# Micro-Controller_Unit.net
KiCad netlist of a schematic drawn in Altium Designer
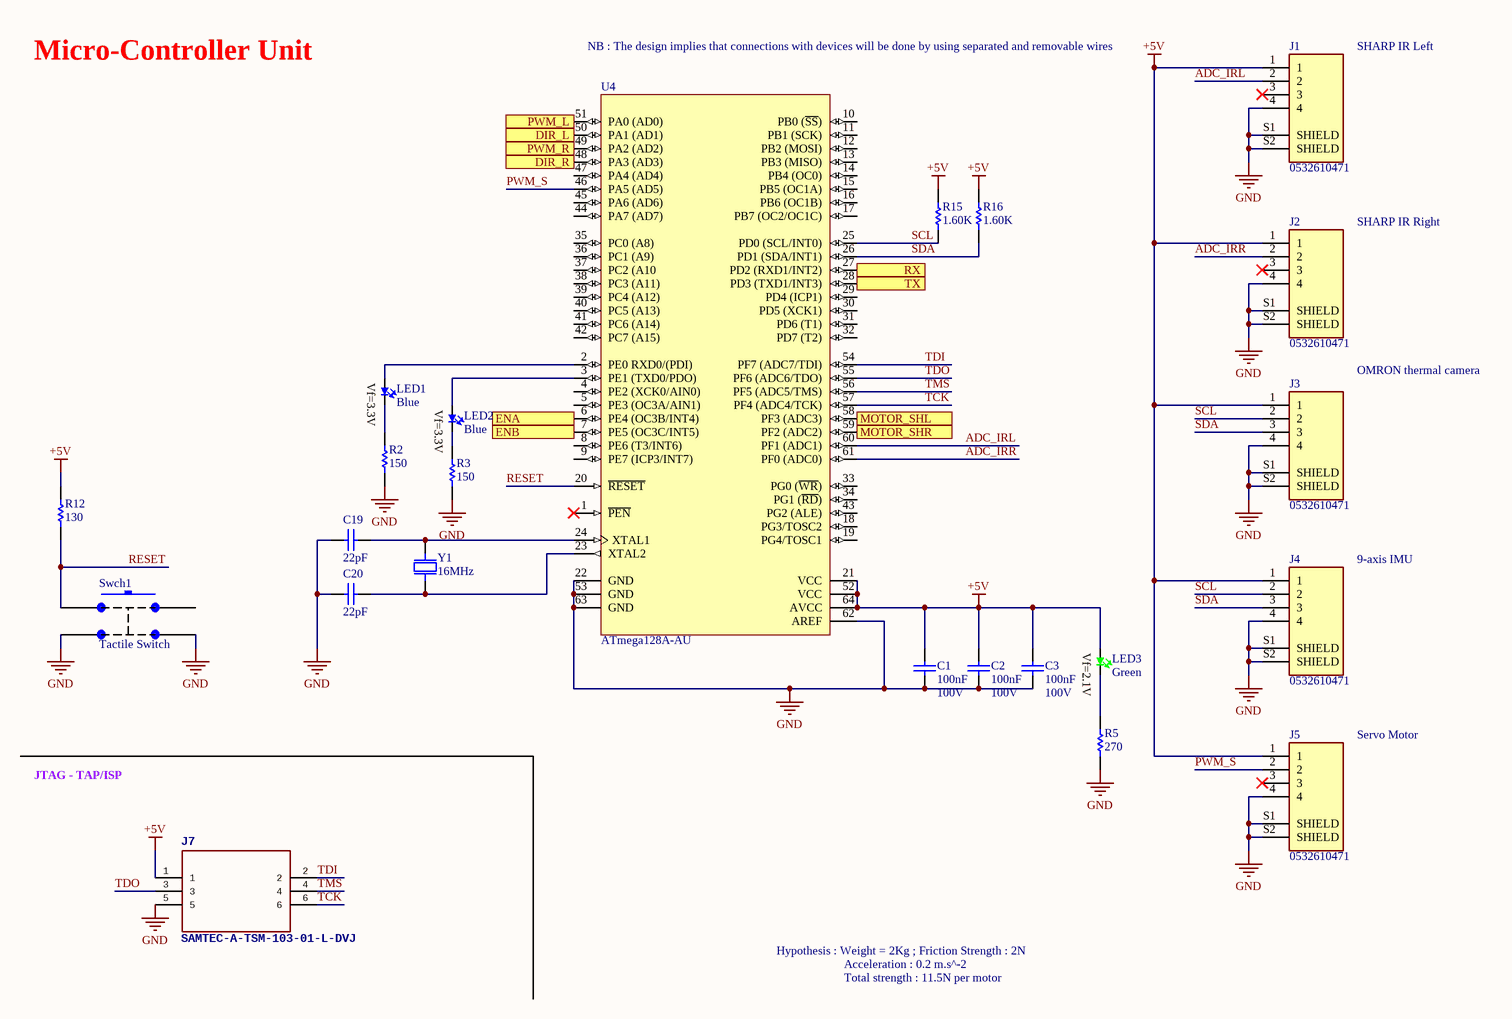
[diagram p0: Micro-Controller Unit.SchDoc]

(export (version "E")
  (design (tool "Eeschema 10.0.6"))
  (components
    (comp (ref "C1")
      (value "100nF")
      (footprint "CC0603 x 0.95mm")
      (description "0.1µF ±10% 100V Ceramic Capacitor X7R 0603 (1608 Metric)")
      (fields
        (field (name "MANUFACTURER") "Yageo")
        (field (name "PART NUMBER") "CS0603KRX7R0BB104")
        (field (name "VOLTAGE - RATED") "100V")
      )
      (libsource (lib "MLCC") (part "CAP"))
    )
    (comp (ref "C2")
      (value "100nF")
      (footprint "CAP-SMT:CC0603 x 0.95mm")
      (description "0.1µF ±10% 100V Ceramic Capacitor X7R 0603 (1608 Metric)")
      (fields
        (field (name "MANUFACTURER") "Yageo")
        (field (name "PART NUMBER") "CS0603KRX7R0BB104")
        (field (name "VOLTAGE - RATED") "100V")
      )
      (libsource (lib "MLCC") (part "CAP"))
    )
    (comp (ref "C3")
      (value "100nF")
      (footprint "CAP-SMT:CC0603 x 0.95mm")
      (description "0.1µF ±10% 100V Ceramic Capacitor X7R 0603 (1608 Metric)")
      (fields
        (field (name "MANUFACTURER") "Yageo")
        (field (name "PART NUMBER") "CS0603KRX7R0BB104")
        (field (name "VOLTAGE - RATED") "100V")
      )
      (libsource (lib "MLCC") (part "CAP"))
    )
    (comp (ref "C19")
      (value "22pF")
      (footprint "CC0201 x 0.33mm")
      (description "22pF ±2% 50V Ceramic Capacitor C0G, NP0 0201 (0603 Metric)")
      (fields (field (name "MANUFACTURER") "Yageo") (field (name "PART NUMBER") "CC0201GRNPO9BN220"))
      (libsource (lib "MLCC") (part "CAP"))
    )
    (comp (ref "C20")
      (value "22pF")
      (footprint "CC0201 x 0.33mm")
      (description "22pF ±2% 50V Ceramic Capacitor C0G, NP0 0201 (0603 Metric)")
      (fields (field (name "MANUFACTURER") "Yageo") (field (name "PART NUMBER") "CC0201GRNPO9BN220"))
      (libsource (lib "MLCC") (part "CAP"))
    )
    (comp (ref "J1")
      (value "0532610471")
      (footprint "MOLEX_0532610471")
      (description "Picoblade Connector, 4 Circuit Single Row, Right Angle Surface Mount SMT PCB")
      (fields (field (name "DIGI-KEY_PART_NUMBER") "WM7622CT-ND") (field (name "MF") "Molex"))
      (libsource (lib "0532610471") (part "0532610471"))
    )
    (comp (ref "J2")
      (value "0532610471")
      (footprint "MOLEX_0532610471")
      (description "Picoblade Connector, 4 Circuit Single Row, Right Angle Surface Mount SMT PCB")
      (fields (field (name "DIGI-KEY_PART_NUMBER") "WM7622CT-ND") (field (name "MF") "Molex"))
      (libsource (lib "0532610471") (part "0532610471"))
    )
    (comp (ref "J3")
      (value "0532610471")
      (footprint "MOLEX_0532610471")
      (description "Picoblade Connector, 4 Circuit Single Row, Right Angle Surface Mount SMT PCB")
      (fields (field (name "DIGI-KEY_PART_NUMBER") "WM7622CT-ND") (field (name "MF") "Molex"))
      (libsource (lib "0532610471") (part "0532610471"))
    )
    (comp (ref "J4")
      (value "0532610471")
      (footprint "MOLEX_0532610471")
      (description "Picoblade Connector, 4 Circuit Single Row, Right Angle Surface Mount SMT PCB")
      (fields (field (name "DIGI-KEY_PART_NUMBER") "WM7622CT-ND") (field (name "MF") "Molex"))
      (libsource (lib "0532610471") (part "0532610471"))
    )
    (comp (ref "J5")
      (value "0532610471")
      (footprint "MOLEX_0532610471")
      (description "Picoblade Connector, 4 Circuit Single Row, Right Angle Surface Mount SMT PCB")
      (fields (field (name "DIGI-KEY_PART_NUMBER") "WM7622CT-ND") (field (name "MF") "Molex"))
      (libsource (lib "0532610471") (part "0532610471"))
    )
    (comp (ref "J7")
      (value "SAMTEC-A-TSM-103-01-L-DVJ")
      (footprint "SAMTEC-A-TSM-103-01-L-DV")
      (libsource (lib "SAMTEC-A-TSM-103-01-L-DV") (part "SAMTEC-A-TSM-103-01-L-DVJ"))
    )
    (comp (ref "LED1")
      (value "Blue")
      (footprint "LED 0603 WHITE")
      (description "1.6 mm x 0.8 mm Blue SMD Top LED")
      (fields (field (name "AVNET PART NUMBER") "KINKP1608QBCD") (field (name "MANUFACTURER") "Kingbright"))
      (libsource (lib "Kingbright") (part "KP-1608QBC-D"))
    )
    (comp (ref "LED2")
      (value "Blue")
      (footprint "LED 0603 WHITE")
      (description "1.6 mm x 0.8 mm Blue SMD Top LED")
      (fields (field (name "AVNET PART NUMBER") "KINKP1608QBCD") (field (name "MANUFACTURER") "Kingbright"))
      (libsource (lib "Kingbright") (part "KP-1608QBC-D"))
    )
    (comp (ref "LED3")
      (value "Green")
      (footprint "LED 0603 GREEN")
      (description "1.6 mm x 0.8 mm Green SMD Top LED")
      (fields (field (name "MANUFACTURER") "Kingbright") (field (name "PART NUMBER") "KP-1608CGCK"))
      (libsource (lib "Kingbright") (part "KP-1608CGCK"))
    )
    (comp (ref "R2")
      (value "150")
      (footprint "RESC0603_N")
      (description "RES 150 OHM 1/10W 1% 0603 SMD")
      (fields (field (name "PART NUMBER") "RC0603FR-07150RL") (field (name "MANUFACTURER") "Yageo"))
      (libsource (lib "RES-SMT") (part "RES"))
    )
    (comp (ref "R3")
      (value "150")
      (footprint "RESC0603_N")
      (description "RES 150 OHM 1/10W 1% 0603 SMD")
      (fields (field (name "PART NUMBER") "RC0603FR-07150RL") (field (name "MANUFACTURER") "Yageo"))
      (libsource (lib "RES-SMT") (part "RES"))
    )
    (comp (ref "R5")
      (value "270")
      (footprint "RESC0603_N")
      (description "RES 270 OHM 1/10W .1% SMD 0603")
      (fields (field (name "PART NUMBER") "RT0603BRE07270RL") (field (name "MANUFACTURER") "Yageo"))
      (libsource (lib "RES-SMT") (part "RES"))
    )
    (comp (ref "R12")
      (value "130")
      (footprint "RESC0603_N")
      (description "RES 130 OHM 1/10W 1% 0603 SMD")
      (fields (field (name "PART NUMBER") "RC0603FR-07130RL") (field (name "MANUFACTURER") "Yageo"))
      (libsource (lib "RES-SMT") (part "RES"))
    )
    (comp (ref "R15")
      (value "1.60K")
      (footprint "RESC0603_N")
      (description "RES 1.60K OHM 1/10W 1% 0603 SMD")
      (fields (field (name "PART NUMBER") "RC0603FR-071K6L") (field (name "MANUFACTURER") "Yageo"))
      (libsource (lib "RES-SMT") (part "RES"))
    )
    (comp (ref "R16")
      (value "1.60K")
      (footprint "RESC0603_N")
      (description "RES 1.60K OHM 1/10W 1% 0603 SMD")
      (fields (field (name "PART NUMBER") "RC0603FR-071K6L") (field (name "MANUFACTURER") "Yageo"))
      (libsource (lib "RES-SMT") (part "RES"))
    )
    (comp (ref "Swch1")
      (value "Tactile Switch")
      (footprint "Tactile Switch - 1825910_6")
      (libsource (lib "Tactile Switch - 1825910_-") (part "Tactile Switch"))
    )
    (comp (ref "U4")
      (value "ATmega128A-AU")
      (footprint "64A_N")
      (fields (field (name "PUBLISHER") "Altium Limited"))
      (libsource (lib "Atmel Microcontroller 8-Bit megaAVR") (part "ATmega128A-AU"))
    )
    (comp (ref "Y1")
      (value "16MHz")
      (footprint "ABM3")
      (description "5.0 X 3.2 X 1.3mm Crystal 8MHz, CL 18pF, 20ppm")
      (fields (field (name "MANUFACTURER") "Abracon") (field (name "PART NUMBER") "ABM3-8.000MHZ-D2Y-T"))
      (libsource (lib "abracon") (part "ABM3-8.000MHZ-D2Y-T"))
    )
  )
  (nets
    (net (code "1") (name "+5V") (class "Default")
      (node (ref "C1") (pin "2") (pinfunction "2_2") (pintype "passive"))
      (node (ref "C2") (pin "2") (pinfunction "2_2") (pintype "passive"))
      (node (ref "C3") (pin "2") (pinfunction "2_2") (pintype "passive"))
      (node (ref "J1") (pin "1") (pinfunction "1_1") (pintype "passive"))
      (node (ref "J2") (pin "1") (pinfunction "1_1") (pintype "passive"))
      (node (ref "J3") (pin "1") (pinfunction "1_1") (pintype "passive"))
      (node (ref "J4") (pin "1") (pinfunction "1_1") (pintype "passive"))
      (node (ref "J5") (pin "1") (pinfunction "1_1") (pintype "passive"))
      (node (ref "J7") (pin "1") (pinfunction "1_1") (pintype "passive"))
      (node (ref "LED3") (pin "2") (pinfunction "A_2") (pintype "passive"))
      (node (ref "R12") (pin "2") (pinfunction "2_2") (pintype "passive"))
      (node (ref "R15") (pin "2") (pinfunction "2_2") (pintype "passive"))
      (node (ref "R16") (pin "2") (pinfunction "2_2") (pintype "passive"))
      (node (ref "U4") (pin "21") (pinfunction "VCC_21") (pintype "power_in"))
      (node (ref "U4") (pin "52") (pinfunction "VCC_52") (pintype "power_in"))
      (node (ref "U4") (pin "64") (pinfunction "AVCC_64") (pintype "power_in"))
    )
    (net (code "2") (name "/ADC_IRL") (class "Default")
      (node (ref "J1") (pin "2") (pinfunction "2_2") (pintype "passive"))
      (node (ref "U4") (pin "60") (pinfunction "PF1_(ADC1)_60") (pintype "bidirectional"))
    )
    (net (code "3") (name "/ADC_IRR") (class "Default")
      (node (ref "J2") (pin "2") (pinfunction "2_2") (pintype "passive"))
      (node (ref "U4") (pin "61") (pinfunction "PF0_(ADC0)_61") (pintype "bidirectional"))
    )
    (net (code "4") (name "/DIR_L") (class "Default")
      (node (ref "U4") (pin "50") (pinfunction "PA1_(AD1)_50") (pintype "bidirectional"))
    )
    (net (code "5") (name "/DIR_R") (class "Default")
      (node (ref "U4") (pin "48") (pinfunction "PA3_(AD3)_48") (pintype "bidirectional"))
    )
    (net (code "6") (name "/ENA") (class "Default")
      (node (ref "U4") (pin "6") (pinfunction "PE4_(OC3B/INT4)_6") (pintype "bidirectional"))
    )
    (net (code "7") (name "/ENB") (class "Default")
      (node (ref "U4") (pin "7") (pinfunction "PE5_(OC3C/INT5)_7") (pintype "bidirectional"))
    )
    (net (code "8") (name "/MOTOR_SHL") (class "Default")
      (node (ref "U4") (pin "58") (pinfunction "PF3_(ADC3)_58") (pintype "bidirectional"))
    )
    (net (code "9") (name "/MOTOR_SHR") (class "Default")
      (node (ref "U4") (pin "59") (pinfunction "PF2_(ADC2)_59") (pintype "bidirectional"))
    )
    (net (code "10") (name "/PWM_L") (class "Default")
      (node (ref "U4") (pin "51") (pinfunction "PA0_(AD0)_51") (pintype "bidirectional"))
    )
    (net (code "11") (name "/PWM_R") (class "Default")
      (node (ref "U4") (pin "49") (pinfunction "PA2_(AD2)_49") (pintype "bidirectional"))
    )
    (net (code "12") (name "/PWM_S") (class "Default")
      (node (ref "J5") (pin "2") (pinfunction "2_2") (pintype "passive"))
      (node (ref "U4") (pin "46") (pinfunction "PA5_(AD5)_46") (pintype "bidirectional"))
    )
    (net (code "13") (name "/RESET") (class "Default")
      (node (ref "R12") (pin "1") (pinfunction "1_1") (pintype "passive"))
      (node (ref "Swch1") (pin "1") (pinfunction "in_1") (pintype "passive"))
      (node (ref "U4") (pin "20") (pinfunction "~{RESET}_20") (pintype "input"))
    )
    (net (code "14") (name "/RX") (class "Default")
      (node (ref "U4") (pin "27") (pinfunction "PD2_(RXD1/INT2)_27") (pintype "bidirectional"))
    )
    (net (code "15") (name "/SCL") (class "Default")
      (node (ref "J3") (pin "2") (pinfunction "2_2") (pintype "passive"))
      (node (ref "J4") (pin "2") (pinfunction "2_2") (pintype "passive"))
      (node (ref "R15") (pin "1") (pinfunction "1_1") (pintype "passive"))
      (node (ref "U4") (pin "25") (pinfunction "PD0_(SCL/INT0)_25") (pintype "bidirectional"))
    )
    (net (code "16") (name "/SDA") (class "Default")
      (node (ref "J3") (pin "3") (pinfunction "3_3") (pintype "passive"))
      (node (ref "J4") (pin "3") (pinfunction "3_3") (pintype "passive"))
      (node (ref "R16") (pin "1") (pinfunction "1_1") (pintype "passive"))
      (node (ref "U4") (pin "26") (pinfunction "PD1_(SDA/INT1)_26") (pintype "bidirectional"))
    )
    (net (code "17") (name "/TCK") (class "Default")
      (node (ref "J7") (pin "6") (pinfunction "6_6") (pintype "passive"))
      (node (ref "U4") (pin "57") (pinfunction "PF4_(ADC4/TCK)_57") (pintype "bidirectional"))
    )
    (net (code "18") (name "/TDI") (class "Default")
      (node (ref "J7") (pin "2") (pinfunction "2_2") (pintype "passive"))
      (node (ref "U4") (pin "54") (pinfunction "PF7_(ADC7/TDI)_54") (pintype "bidirectional"))
    )
    (net (code "19") (name "/TDO") (class "Default")
      (node (ref "J7") (pin "3") (pinfunction "3_3") (pintype "passive"))
      (node (ref "U4") (pin "55") (pinfunction "PF6_(ADC6/TDO)_55") (pintype "bidirectional"))
    )
    (net (code "20") (name "/TMS") (class "Default")
      (node (ref "J7") (pin "4") (pinfunction "4_4") (pintype "passive"))
      (node (ref "U4") (pin "56") (pinfunction "PF5_(ADC5/TMS)_56") (pintype "bidirectional"))
    )
    (net (code "21") (name "/TX") (class "Default")
      (node (ref "U4") (pin "28") (pinfunction "PD3_(TXD1/INT3)_28") (pintype "bidirectional"))
    )
    (net (code "22") (name "GND") (class "Default")
      (node (ref "C1") (pin "1") (pinfunction "1_1") (pintype "passive"))
      (node (ref "C19") (pin "1") (pinfunction "1_1") (pintype "passive"))
      (node (ref "C2") (pin "1") (pinfunction "1_1") (pintype "passive"))
      (node (ref "C20") (pin "1") (pinfunction "1_1") (pintype "passive"))
      (node (ref "C3") (pin "1") (pinfunction "1_1") (pintype "passive"))
      (node (ref "J1") (pin "4") (pinfunction "4_4") (pintype "passive"))
      (node (ref "J1") (pin "S1") (pinfunction "SHIELD_S1") (pintype "passive"))
      (node (ref "J1") (pin "S2") (pinfunction "SHIELD_S2") (pintype "passive"))
      (node (ref "J2") (pin "4") (pinfunction "4_4") (pintype "passive"))
      (node (ref "J2") (pin "S1") (pinfunction "SHIELD_S1") (pintype "passive"))
      (node (ref "J2") (pin "S2") (pinfunction "SHIELD_S2") (pintype "passive"))
      (node (ref "J3") (pin "4") (pinfunction "4_4") (pintype "passive"))
      (node (ref "J3") (pin "S1") (pinfunction "SHIELD_S1") (pintype "passive"))
      (node (ref "J3") (pin "S2") (pinfunction "SHIELD_S2") (pintype "passive"))
      (node (ref "J4") (pin "4") (pinfunction "4_4") (pintype "passive"))
      (node (ref "J4") (pin "S1") (pinfunction "SHIELD_S1") (pintype "passive"))
      (node (ref "J4") (pin "S2") (pinfunction "SHIELD_S2") (pintype "passive"))
      (node (ref "J5") (pin "4") (pinfunction "4_4") (pintype "passive"))
      (node (ref "J5") (pin "S1") (pinfunction "SHIELD_S1") (pintype "passive"))
      (node (ref "J5") (pin "S2") (pinfunction "SHIELD_S2") (pintype "passive"))
      (node (ref "J7") (pin "5") (pinfunction "5_5") (pintype "passive"))
      (node (ref "R2") (pin "1") (pinfunction "1_1") (pintype "passive"))
      (node (ref "R3") (pin "1") (pinfunction "1_1") (pintype "passive"))
      (node (ref "R5") (pin "1") (pinfunction "1_1") (pintype "passive"))
      (node (ref "Swch1") (pin "3") (pinfunction "out_3") (pintype "passive"))
      (node (ref "Swch1") (pin "4") (pinfunction "out_4") (pintype "passive"))
      (node (ref "U4") (pin "22") (pinfunction "GND_22") (pintype "power_in"))
      (node (ref "U4") (pin "53") (pinfunction "GND_53") (pintype "power_in"))
      (node (ref "U4") (pin "62") (pinfunction "AREF_62") (pintype "power_in"))
      (node (ref "U4") (pin "63") (pinfunction "GND_63") (pintype "power_in"))
    )
    (net (code "23") (name "Net-(LED1-A)") (class "Default")
      (node (ref "LED1") (pin "2") (pinfunction "A_2") (pintype "passive"))
      (node (ref "U4") (pin "2") (pinfunction "PE0_RXD0/(PDI)_2") (pintype "bidirectional"))
    )
    (net (code "24") (name "Net-(LED1-K)") (class "Default")
      (node (ref "LED1") (pin "1") (pinfunction "K_1") (pintype "passive"))
      (node (ref "R2") (pin "2") (pinfunction "2_2") (pintype "passive"))
    )
    (net (code "25") (name "Net-(LED2-A)") (class "Default")
      (node (ref "LED2") (pin "2") (pinfunction "A_2") (pintype "passive"))
      (node (ref "U4") (pin "3") (pinfunction "PE1_(TXD0/PDO)_3") (pintype "bidirectional"))
    )
    (net (code "26") (name "Net-(LED2-K)") (class "Default")
      (node (ref "LED2") (pin "1") (pinfunction "K_1") (pintype "passive"))
      (node (ref "R3") (pin "2") (pinfunction "2_2") (pintype "passive"))
    )
    (net (code "27") (name "Net-(LED3-K)") (class "Default")
      (node (ref "LED3") (pin "1") (pinfunction "K_1") (pintype "passive"))
      (node (ref "R5") (pin "2") (pinfunction "2_2") (pintype "passive"))
    )
    (net (code "28") (name "Net-(U4-XTAL1)") (class "Default")
      (node (ref "C19") (pin "2") (pinfunction "2_2") (pintype "passive"))
      (node (ref "U4") (pin "24") (pinfunction "XTAL1_24") (pintype "input"))
      (node (ref "Y1") (pin "2") (pinfunction "2_2") (pintype "passive"))
    )
    (net (code "29") (name "Net-(U4-XTAL2)") (class "Default")
      (node (ref "C20") (pin "2") (pinfunction "2_2") (pintype "passive"))
      (node (ref "U4") (pin "23") (pinfunction "XTAL2_23") (pintype "output"))
      (node (ref "Y1") (pin "1") (pinfunction "1_1") (pintype "passive"))
    )
    (net (code "30") (name "unconnected-(J1-Pad3)") (class "Default")
      (node (ref "J1") (pin "3") (pinfunction "3_3") (pintype "passive+no_connect"))
    )
    (net (code "31") (name "unconnected-(J2-Pad3)") (class "Default")
      (node (ref "J2") (pin "3") (pinfunction "3_3") (pintype "passive+no_connect"))
    )
    (net (code "32") (name "unconnected-(J5-Pad3)") (class "Default")
      (node (ref "J5") (pin "3") (pinfunction "3_3") (pintype "passive+no_connect"))
    )
    (net (code "33") (name "unconnected-(Swch1-in-Pad2)") (class "Default")
      (node (ref "Swch1") (pin "2") (pinfunction "in_2") (pintype "passive"))
    )
    (net (code "34") (name "unconnected-(U4-PA4_(AD4)-Pad47)") (class "Default")
      (node (ref "U4") (pin "47") (pinfunction "PA4_(AD4)_47") (pintype "bidirectional"))
    )
    (net (code "35") (name "unconnected-(U4-PA6_(AD6)-Pad45)") (class "Default")
      (node (ref "U4") (pin "45") (pinfunction "PA6_(AD6)_45") (pintype "bidirectional"))
    )
    (net (code "36") (name "unconnected-(U4-PA7_(AD7)-Pad44)") (class "Default")
      (node (ref "U4") (pin "44") (pinfunction "PA7_(AD7)_44") (pintype "bidirectional"))
    )
    (net (code "37") (name "unconnected-(U4-PB0_(~{SS})-Pad10)") (class "Default")
      (node (ref "U4") (pin "10") (pinfunction "PB0_(~{SS})_10") (pintype "bidirectional"))
    )
    (net (code "38") (name "unconnected-(U4-PB1_(SCK)-Pad11)") (class "Default")
      (node (ref "U4") (pin "11") (pinfunction "PB1_(SCK)_11") (pintype "bidirectional"))
    )
    (net (code "39") (name "unconnected-(U4-PB2_(MOSI)-Pad12)") (class "Default")
      (node (ref "U4") (pin "12") (pinfunction "PB2_(MOSI)_12") (pintype "bidirectional"))
    )
    (net (code "40") (name "unconnected-(U4-PB3_(MISO)-Pad13)") (class "Default")
      (node (ref "U4") (pin "13") (pinfunction "PB3_(MISO)_13") (pintype "bidirectional"))
    )
    (net (code "41") (name "unconnected-(U4-PB4_(OC0)-Pad14)") (class "Default")
      (node (ref "U4") (pin "14") (pinfunction "PB4_(OC0)_14") (pintype "bidirectional"))
    )
    (net (code "42") (name "unconnected-(U4-PB5_(OC1A)-Pad15)") (class "Default")
      (node (ref "U4") (pin "15") (pinfunction "PB5_(OC1A)_15") (pintype "bidirectional"))
    )
    (net (code "43") (name "unconnected-(U4-PB6_(OC1B)-Pad16)") (class "Default")
      (node (ref "U4") (pin "16") (pinfunction "PB6_(OC1B)_16") (pintype "bidirectional"))
    )
    (net (code "44") (name "unconnected-(U4-PB7_(OC2{slash}OC1C)-Pad17)") (class "Default")
      (node (ref "U4") (pin "17") (pinfunction "PB7_(OC2/OC1C)_17") (pintype "bidirectional"))
    )
    (net (code "45") (name "unconnected-(U4-PC0_(A8)-Pad35)") (class "Default")
      (node (ref "U4") (pin "35") (pinfunction "PC0_(A8)_35") (pintype "bidirectional"))
    )
    (net (code "46") (name "unconnected-(U4-PC1_(A9)-Pad36)") (class "Default")
      (node (ref "U4") (pin "36") (pinfunction "PC1_(A9)_36") (pintype "bidirectional"))
    )
    (net (code "47") (name "unconnected-(U4-PC2_(A10-Pad37)") (class "Default")
      (node (ref "U4") (pin "37") (pinfunction "PC2_(A10_37") (pintype "bidirectional"))
    )
    (net (code "48") (name "unconnected-(U4-PC3_(A11)-Pad38)") (class "Default")
      (node (ref "U4") (pin "38") (pinfunction "PC3_(A11)_38") (pintype "bidirectional"))
    )
    (net (code "49") (name "unconnected-(U4-PC4_(A12)-Pad39)") (class "Default")
      (node (ref "U4") (pin "39") (pinfunction "PC4_(A12)_39") (pintype "bidirectional"))
    )
    (net (code "50") (name "unconnected-(U4-PC5_(A13)-Pad40)") (class "Default")
      (node (ref "U4") (pin "40") (pinfunction "PC5_(A13)_40") (pintype "bidirectional"))
    )
    (net (code "51") (name "unconnected-(U4-PC6_(A14)-Pad41)") (class "Default")
      (node (ref "U4") (pin "41") (pinfunction "PC6_(A14)_41") (pintype "bidirectional"))
    )
    (net (code "52") (name "unconnected-(U4-PC7_(A15)-Pad42)") (class "Default")
      (node (ref "U4") (pin "42") (pinfunction "PC7_(A15)_42") (pintype "bidirectional"))
    )
    (net (code "53") (name "unconnected-(U4-PD4_(ICP1)-Pad29)") (class "Default")
      (node (ref "U4") (pin "29") (pinfunction "PD4_(ICP1)_29") (pintype "bidirectional"))
    )
    (net (code "54") (name "unconnected-(U4-PD5_(XCK1)-Pad30)") (class "Default")
      (node (ref "U4") (pin "30") (pinfunction "PD5_(XCK1)_30") (pintype "bidirectional"))
    )
    (net (code "55") (name "unconnected-(U4-PD6_(T1)-Pad31)") (class "Default")
      (node (ref "U4") (pin "31") (pinfunction "PD6_(T1)_31") (pintype "bidirectional"))
    )
    (net (code "56") (name "unconnected-(U4-PD7_(T2)-Pad32)") (class "Default")
      (node (ref "U4") (pin "32") (pinfunction "PD7_(T2)_32") (pintype "bidirectional"))
    )
    (net (code "57") (name "unconnected-(U4-PE2_(XCK0{slash}AIN0)-Pad4)") (class "Default")
      (node (ref "U4") (pin "4") (pinfunction "PE2_(XCK0/AIN0)_4") (pintype "bidirectional"))
    )
    (net (code "58") (name "unconnected-(U4-PE3_(OC3A{slash}AIN1)-Pad5)") (class "Default")
      (node (ref "U4") (pin "5") (pinfunction "PE3_(OC3A/AIN1)_5") (pintype "bidirectional"))
    )
    (net (code "59") (name "unconnected-(U4-PE6_(T3{slash}INT6)-Pad8)") (class "Default")
      (node (ref "U4") (pin "8") (pinfunction "PE6_(T3/INT6)_8") (pintype "bidirectional"))
    )
    (net (code "60") (name "unconnected-(U4-PE7_(ICP3{slash}INT7)-Pad9)") (class "Default")
      (node (ref "U4") (pin "9") (pinfunction "PE7_(ICP3/INT7)_9") (pintype "bidirectional"))
    )
    (net (code "61") (name "unconnected-(U4-PG0_(~{WR})-Pad33)") (class "Default")
      (node (ref "U4") (pin "33") (pinfunction "PG0_(~{WR})_33") (pintype "bidirectional"))
    )
    (net (code "62") (name "unconnected-(U4-PG1_(~{RD})-Pad34)") (class "Default")
      (node (ref "U4") (pin "34") (pinfunction "PG1_(~{RD})_34") (pintype "bidirectional"))
    )
    (net (code "63") (name "unconnected-(U4-PG2_(ALE)-Pad43)") (class "Default")
      (node (ref "U4") (pin "43") (pinfunction "PG2_(ALE)_43") (pintype "bidirectional"))
    )
    (net (code "64") (name "unconnected-(U4-PG3{slash}TOSC2-Pad18)") (class "Default")
      (node (ref "U4") (pin "18") (pinfunction "PG3/TOSC2_18") (pintype "bidirectional"))
    )
    (net (code "65") (name "unconnected-(U4-PG4{slash}TOSC1-Pad19)") (class "Default")
      (node (ref "U4") (pin "19") (pinfunction "PG4/TOSC1_19") (pintype "bidirectional"))
    )
    (net (code "66") (name "unconnected-(U4-~{PEN}-Pad1)") (class "Default")
      (node (ref "U4") (pin "1") (pinfunction "~{PEN}_1") (pintype "input+no_connect"))
    )
  )
)
